# power.net
KiCad netlist of a schematic drawn in Altium Designer
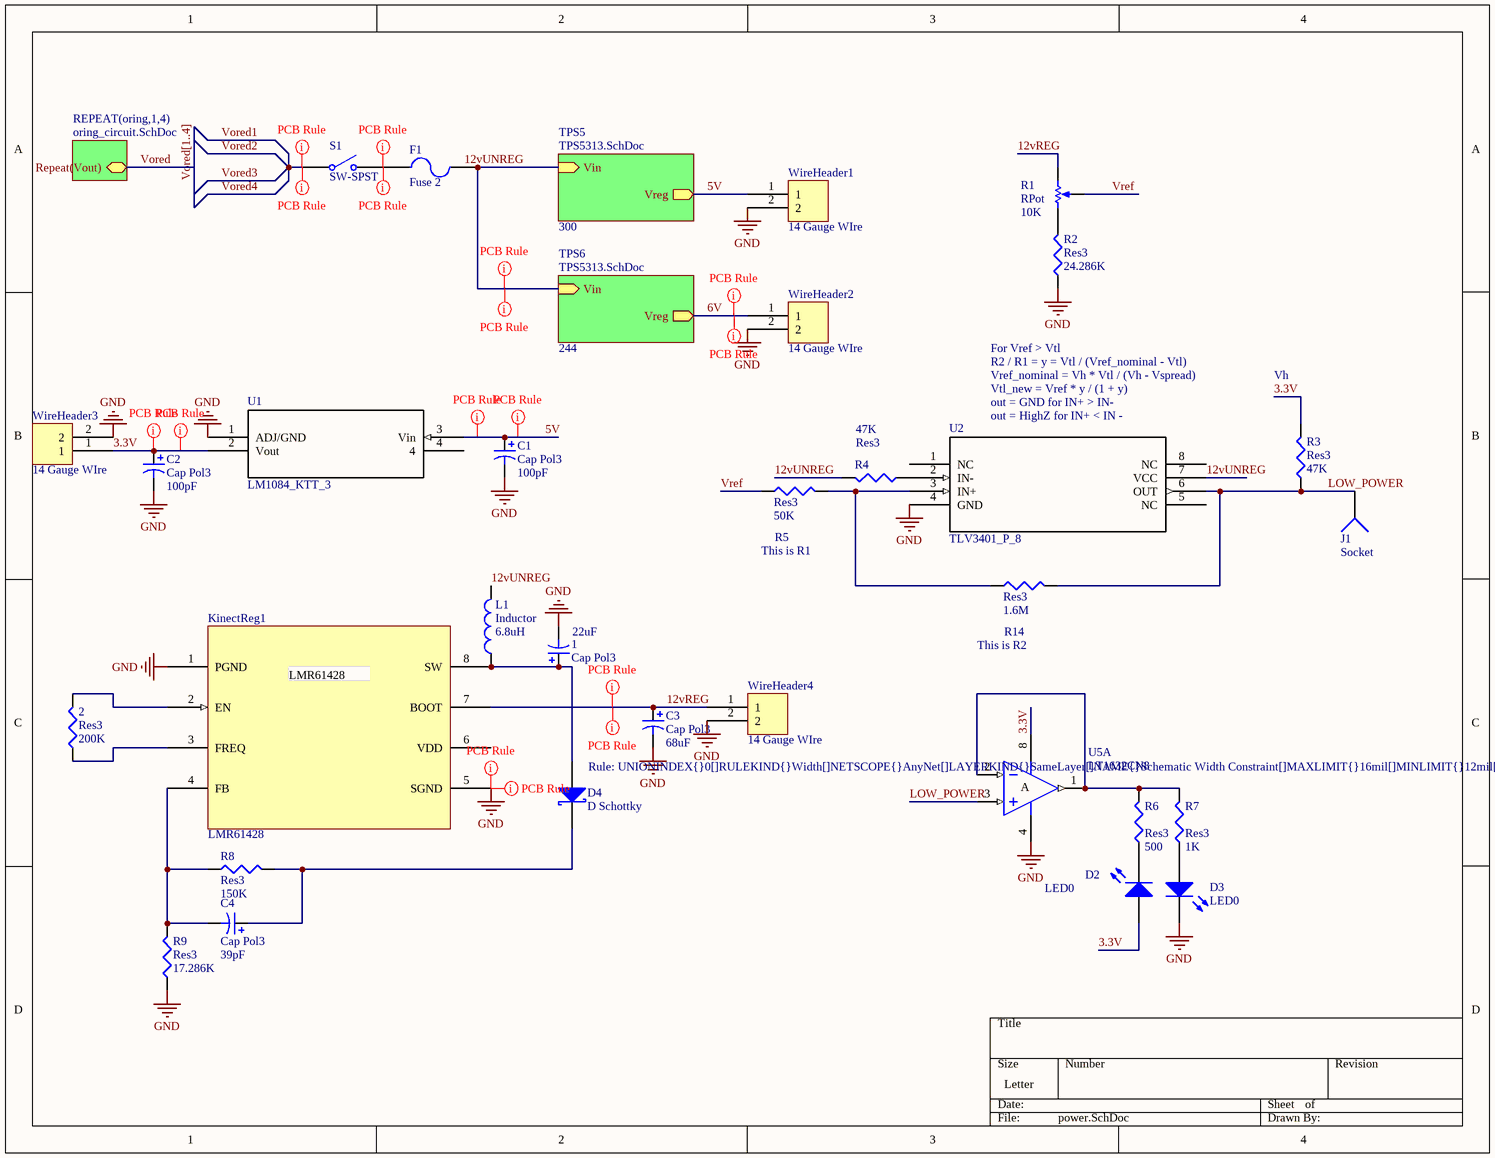
[diagram p0: power.SchDoc]

(export (version "E")
  (design (tool "Eeschema 10.0.6"))
  (components
    (comp (ref "1")
      (value "Cap Pol3")
      (footprint "C0805")
      (description "Polarized Capacitor (Surface Mount)")
      (fields (field (name "ALTIUM_VALUE") "22uF") (field (name "PUBLISHER") "Altium Limited"))
      (libsource (lib "Miscellaneous Devices") (part "Cap Pol3"))
    )
    (comp (ref "2")
      (value "Res3")
      (footprint "6-0805_M")
      (description "Resistor")
      (fields (field (name "ALTIUM_VALUE") "200K") (field (name "PUBLISHER") "Altium Limited"))
      (libsource (lib "Miscellaneous Devices") (part "Res3"))
    )
    (comp (ref "C1")
      (value "Cap Pol3")
      (footprint "C0805")
      (description "Polarized Capacitor (Surface Mount)")
      (fields (field (name "ALTIUM_VALUE") "100pF") (field (name "PUBLISHER") "Altium Limited"))
      (libsource (lib "Miscellaneous Devices") (part "Cap Pol3"))
    )
    (comp (ref "C2")
      (value "Cap Pol3")
      (footprint "C0805")
      (description "Polarized Capacitor (Surface Mount)")
      (fields (field (name "ALTIUM_VALUE") "100pF") (field (name "PUBLISHER") "Altium Limited"))
      (libsource (lib "Miscellaneous Devices") (part "Cap Pol3"))
    )
    (comp (ref "C3")
      (value "Cap Pol3")
      (footprint "C0805")
      (description "Polarized Capacitor (Surface Mount)")
      (fields (field (name "ALTIUM_VALUE") "68uF") (field (name "PUBLISHER") "Altium Limited"))
      (libsource (lib "Miscellaneous Devices") (part "Cap Pol3"))
    )
    (comp (ref "C4")
      (value "Cap Pol3")
      (footprint "C0805")
      (description "Polarized Capacitor (Surface Mount)")
      (fields (field (name "ALTIUM_VALUE") "39pF") (field (name "PUBLISHER") "Altium Limited"))
      (libsource (lib "Miscellaneous Devices") (part "Cap Pol3"))
    )
    (comp (ref "D2")
      (value "LED0")
      (footprint "LED-0")
      (description "Typical INFRARED GaAs LED")
      (fields (field (name "PUBLISHER") "Altium Limited"))
      (libsource (lib "Miscellaneous Devices") (part "LED0"))
    )
    (comp (ref "D3")
      (value "LED0")
      (footprint "LED-0")
      (description "Typical INFRARED GaAs LED")
      (fields (field (name "PUBLISHER") "Altium Limited"))
      (libsource (lib "Miscellaneous Devices") (part "LED0"))
    )
    (comp (ref "D4")
      (value "D Schottky")
      (footprint "AXIAL-0.3")
      (description "Schottky Diode")
      (fields (field (name "PUBLISHER") "Altium Limited"))
      (libsource (lib "Miscellaneous Devices") (part "D Schottky"))
    )
    (comp (ref "F1")
      (value "Fuse 2")
      (footprint "PIN-W2/E2.8")
      (description "Fuse")
      (fields (field (name "PUBLISHER") "Altium Limited"))
      (libsource (lib "Miscellaneous Devices") (part "Fuse 2"))
    )
    (comp (ref "J1")
      (value "Socket")
      (footprint "PIN1")
      (fields (field (name "PUBLISHER") "Altium Limited"))
      (libsource (lib "Miscellaneous Connectors") (part "Socket"))
    )
    (comp (ref "KinectReg1")
      (value "LMR61428")
      (footprint "D8")
      (libsource (lib "InvestiGator") (part "LMR61428"))
    )
    (comp (ref "L1")
      (value "Inductor")
      (footprint "6-0805_L")
      (fields (field (name "ALTIUM_VALUE") "6.8uH") (field (name "PUBLISHER") "Altium Limited"))
      (libsource (lib "Miscellaneous Devices") (part "Inductor"))
    )
    (comp (ref "R1")
      (value "RPot")
      (footprint "RPot")
      (description "Potentiometer")
      (fields (field (name "ALTIUM_VALUE") "10K") (field (name "PUBLISHER") "Altium Limited"))
      (libsource (lib "Miscellaneous Devices") (part "RPot"))
    )
    (comp (ref "R2")
      (value "Res3")
      (footprint "6-0805_M")
      (description "Resistor")
      (fields (field (name "ALTIUM_VALUE") "24.286K") (field (name "PUBLISHER") "Altium Limited"))
      (libsource (lib "Miscellaneous Devices") (part "Res3"))
    )
    (comp (ref "R3")
      (value "Res3")
      (footprint "6-0805_M")
      (description "Resistor")
      (fields (field (name "ALTIUM_VALUE") "47K") (field (name "PUBLISHER") "Altium Limited"))
      (libsource (lib "Miscellaneous Devices") (part "Res3"))
    )
    (comp (ref "R4")
      (value "Res3")
      (footprint "6-0805_M")
      (description "Resistor")
      (fields (field (name "ALTIUM_VALUE") "47K") (field (name "PUBLISHER") "Altium Limited"))
      (libsource (lib "Miscellaneous Devices") (part "Res3"))
    )
    (comp (ref "R5")
      (value "Res3")
      (footprint "6-0805_M")
      (description "Resistor")
      (fields (field (name "ALTIUM_VALUE") "50K") (field (name "PUBLISHER") "Altium Limited"))
      (libsource (lib "Miscellaneous Devices") (part "Res3"))
    )
    (comp (ref "R6")
      (value "Res3")
      (footprint "6-0805_M")
      (description "Resistor")
      (fields (field (name "ALTIUM_VALUE") "500") (field (name "PUBLISHER") "Altium Limited"))
      (libsource (lib "Miscellaneous Devices") (part "Res3"))
    )
    (comp (ref "R7")
      (value "Res3")
      (footprint "6-0805_M")
      (description "Resistor")
      (fields (field (name "ALTIUM_VALUE") "1K") (field (name "PUBLISHER") "Altium Limited"))
      (libsource (lib "Miscellaneous Devices") (part "Res3"))
    )
    (comp (ref "R8")
      (value "Res3")
      (footprint "6-0805_M")
      (description "Resistor")
      (fields (field (name "ALTIUM_VALUE") "150K") (field (name "PUBLISHER") "Altium Limited"))
      (libsource (lib "Miscellaneous Devices") (part "Res3"))
    )
    (comp (ref "R9")
      (value "Res3")
      (footprint "6-0805_M")
      (description "Resistor")
      (fields (field (name "ALTIUM_VALUE") "17.286K") (field (name "PUBLISHER") "Altium Limited"))
      (libsource (lib "Miscellaneous Devices") (part "Res3"))
    )
    (comp (ref "R14")
      (value "Res3")
      (footprint "6-0805_M")
      (description "Resistor")
      (fields (field (name "ALTIUM_VALUE") "1.6M") (field (name "PUBLISHER") "Altium Limited"))
      (libsource (lib "Miscellaneous Devices") (part "Res3"))
    )
    (comp (ref "S1")
      (value "SW-SPST")
      (footprint "switch")
      (description "Single-Pole, Single-Throw Switch")
      (fields (field (name "PUBLISHER") "Altium Limited"))
      (libsource (lib "Miscellaneous Devices") (part "SW-SPST"))
    )
    (comp (ref "U1")
      (value "LM1084_KTT_3")
      (footprint "TS3B")
      (description "Imported")
      (fields (field (name "PARTNUMBER") "LM1084IS-33"))
      (libsource (lib "LM1084") (part "LM1084_KTT_3"))
    )
    (comp (ref "U2")
      (value "TLV3401_P_8")
      (footprint "P8")
      (description "Imported")
      (fields
        (field (name "MANUFACTURER_PART_NUMBER") "tlv3401_p_8")
        (field (name "GENERIC_PART_NUMBER") "TLV3401")
      )
      (libsource (lib "TLV3401P") (part "TLV3401_P_8"))
    )
    (comp (ref "U5")
      (value "LT1632CN8")
      (footprint "P8")
      (description "45MHz, 45V/µs, Dual Rail-to-Rail Input and Output Precision Operational Amplifier")
      (fields (field (name "PUBLISHER") "Altium Limited"))
      (libsource (lib "ECE Lib (1)") (part "LT1632CN8"))
    )
    (comp (ref "WireHeader1")
      (value "14 Gauge WIre")
      (footprint "WireHeader")
      (libsource (lib "InvestiGator") (part "WireHeader"))
    )
    (comp (ref "WireHeader2")
      (value "14 Gauge WIre")
      (footprint "WireHeader")
      (libsource (lib "InvestiGator") (part "WireHeader"))
    )
    (comp (ref "WireHeader3")
      (value "14 Gauge WIre")
      (footprint "WireHeader")
      (libsource (lib "") (part "WireHeader_1"))
    )
    (comp (ref "WireHeader4")
      (value "14 Gauge WIre")
      (footprint "WireHeader")
      (libsource (lib "InvestiGator") (part "WireHeader"))
    )
  )
  (nets
    (net (code "1") (name "/3.3V") (class "Default")
      (node (ref "C2") (pin "1") (pinfunction "1_1") (pintype "passive"))
      (node (ref "D2") (pin "1") (pinfunction "A_1") (pintype "passive"))
      (node (ref "R3") (pin "2") (pinfunction "2_2") (pintype "passive"))
      (node (ref "U1") (pin "2") (pinfunction "Vout_2") (pintype "passive"))
      (node (ref "U5") (pin "8") (pinfunction "V+_8") (pintype "power_in"))
      (node (ref "WireHeader3") (pin "1") (pinfunction "1_1") (pintype "passive"))
    )
    (net (code "2") (name "/5V") (class "Default")
      (node (ref "C1") (pin "1") (pinfunction "1_1") (pintype "passive"))
      (node (ref "U1") (pin "3") (pinfunction "Vin_3") (pintype "input"))
      (node (ref "WireHeader1") (pin "1") (pinfunction "1_1") (pintype "passive"))
    )
    (net (code "3") (name "/6V") (class "Default")
      (node (ref "WireHeader2") (pin "1") (pinfunction "1_1") (pintype "passive"))
    )
    (net (code "4") (name "/12vREG") (class "Default")
      (node (ref "C3") (pin "1") (pinfunction "1_1") (pintype "passive"))
      (node (ref "KinectReg1") (pin "7") (pinfunction "BOOT_7") (pintype "passive"))
      (node (ref "R1") (pin "2") (pinfunction "BOT_2") (pintype "passive"))
      (node (ref "WireHeader4") (pin "1") (pinfunction "1_1") (pintype "passive"))
    )
    (net (code "5") (name "/12vUNREG") (class "Default")
      (node (ref "L1") (pin "2") (pinfunction "2_2") (pintype "passive"))
      (node (ref "R4") (pin "2") (pinfunction "2_2") (pintype "passive"))
      (node (ref "U2") (pin "7") (pinfunction "VCC_7") (pintype "power_in"))
    )
    (net (code "6") (name "/LOW_POWER") (class "Default")
      (node (ref "J1") (pin "1") (pinfunction "1_1") (pintype "passive"))
      (node (ref "R14") (pin "2") (pinfunction "2_2") (pintype "passive"))
      (node (ref "R3") (pin "1") (pinfunction "1_1") (pintype "passive"))
      (node (ref "U2") (pin "6") (pinfunction "OUT_6") (pintype "output"))
      (node (ref "U5") (pin "3") (pinfunction "IN+_3") (pintype "input"))
    )
    (net (code "7") (name "/Vin") (class "Default")
      (node (ref "F1") (pin "2") (pinfunction "2_2") (pintype "passive"))
    )
    (net (code "9") (name "/Vored4") (class "Default")
      (node (ref "S1") (pin "1") (pinfunction "COMMON_1") (pintype "passive"))
    )
    (net (code "11") (name "/Vref") (class "Default")
      (node (ref "R1") (pin "3") (pinfunction "TAP_3") (pintype "passive"))
      (node (ref "R5") (pin "1") (pinfunction "1_1") (pintype "passive"))
    )
    (net (code "12") (name "GND") (class "Default")
      (node (ref "1") (pin "2") (pinfunction "2_2") (pintype "passive"))
      (node (ref "C1") (pin "2") (pinfunction "2_2") (pintype "passive"))
      (node (ref "C2") (pin "2") (pinfunction "2_2") (pintype "passive"))
      (node (ref "C3") (pin "2") (pinfunction "2_2") (pintype "passive"))
      (node (ref "D3") (pin "2") (pinfunction "K_2") (pintype "passive"))
      (node (ref "KinectReg1") (pin "1") (pinfunction "PGND_1") (pintype "power_in"))
      (node (ref "KinectReg1") (pin "5") (pinfunction "SGND_5") (pintype "power_in"))
      (node (ref "R2") (pin "1") (pinfunction "1_1") (pintype "passive"))
      (node (ref "R9") (pin "1") (pinfunction "1_1") (pintype "passive"))
      (node (ref "U1") (pin "1") (pinfunction "ADJ/GND_1") (pintype "passive"))
      (node (ref "U2") (pin "4") (pinfunction "GND_4") (pintype "power_in"))
      (node (ref "U5") (pin "4") (pinfunction "V-_4") (pintype "power_in"))
      (node (ref "WireHeader1") (pin "2") (pinfunction "2_2") (pintype "passive"))
      (node (ref "WireHeader2") (pin "2") (pinfunction "2_2") (pintype "passive"))
      (node (ref "WireHeader3") (pin "2") (pinfunction "2_2") (pintype "passive"))
      (node (ref "WireHeader4") (pin "2") (pinfunction "2_2") (pintype "passive"))
    )
    (net (code "13") (name "Net-(D2-K)") (class "Default")
      (node (ref "D2") (pin "2") (pinfunction "K_2") (pintype "passive"))
      (node (ref "R6") (pin "1") (pinfunction "1_1") (pintype "passive"))
    )
    (net (code "14") (name "Net-(D3-A)") (class "Default")
      (node (ref "D3") (pin "1") (pinfunction "A_1") (pintype "passive"))
      (node (ref "R7") (pin "1") (pinfunction "1_1") (pintype "passive"))
    )
    (net (code "15") (name "Net-(D4-A)") (class "Default")
      (node (ref "1") (pin "1") (pinfunction "1_1") (pintype "passive"))
      (node (ref "D4") (pin "1") (pinfunction "A_1") (pintype "passive"))
      (node (ref "KinectReg1") (pin "8") (pinfunction "SW_8") (pintype "passive"))
      (node (ref "L1") (pin "1") (pinfunction "1_1") (pintype "passive"))
    )
    (net (code "16") (name "Net-(D4-K)") (class "Default")
      (node (ref "C4") (pin "1") (pinfunction "1_1") (pintype "passive"))
      (node (ref "D4") (pin "2") (pinfunction "K_2") (pintype "passive"))
      (node (ref "R8") (pin "2") (pinfunction "2_2") (pintype "passive"))
    )
    (net (code "17") (name "Net-(KinectReg1-EN)") (class "Default")
      (node (ref "2") (pin "2") (pinfunction "2_2") (pintype "passive"))
      (node (ref "KinectReg1") (pin "2") (pinfunction "EN_2") (pintype "input"))
    )
    (net (code "18") (name "Net-(KinectReg1-FB)") (class "Default")
      (node (ref "C4") (pin "2") (pinfunction "2_2") (pintype "passive"))
      (node (ref "KinectReg1") (pin "4") (pinfunction "FB_4") (pintype "passive"))
      (node (ref "R8") (pin "1") (pinfunction "1_1") (pintype "passive"))
      (node (ref "R9") (pin "2") (pinfunction "2_2") (pintype "passive"))
    )
    (net (code "19") (name "Net-(KinectReg1-FREQ)") (class "Default")
      (node (ref "2") (pin "1") (pinfunction "1_1") (pintype "passive"))
      (node (ref "KinectReg1") (pin "3") (pinfunction "FREQ_3") (pintype "passive"))
    )
    (net (code "20") (name "Net-(R1-TOP)") (class "Default")
      (node (ref "R1") (pin "1") (pinfunction "TOP_1") (pintype "passive"))
      (node (ref "R2") (pin "2") (pinfunction "2_2") (pintype "passive"))
    )
    (net (code "21") (name "Net-(S1-NO)") (class "Default")
      (node (ref "F1") (pin "1") (pinfunction "1_1") (pintype "passive"))
      (node (ref "S1") (pin "2") (pinfunction "NO_2") (pintype "passive"))
    )
    (net (code "22") (name "Net-(U2-IN+)") (class "Default")
      (node (ref "R14") (pin "1") (pinfunction "1_1") (pintype "passive"))
      (node (ref "R5") (pin "2") (pinfunction "2_2") (pintype "passive"))
      (node (ref "U2") (pin "3") (pinfunction "IN+_3") (pintype "input"))
    )
    (net (code "23") (name "Net-(U2-IN-)") (class "Default")
      (node (ref "R4") (pin "1") (pinfunction "1_1") (pintype "passive"))
      (node (ref "U2") (pin "2") (pinfunction "IN-_2") (pintype "input"))
    )
    (net (code "24") (name "Net-(U5A-IN-)") (class "Default")
      (node (ref "R6") (pin "2") (pinfunction "2_2") (pintype "passive"))
      (node (ref "R7") (pin "2") (pinfunction "2_2") (pintype "passive"))
      (node (ref "U5") (pin "1") (pinfunction "OUT_1") (pintype "output"))
      (node (ref "U5") (pin "2") (pinfunction "IN-_2") (pintype "input"))
    )
    (net (code "25") (name "unconnected-(KinectReg1-VDD-Pad6)") (class "Default")
      (node (ref "KinectReg1") (pin "6") (pinfunction "VDD_6") (pintype "power_in"))
    )
    (net (code "26") (name "unconnected-(U1-Pad4)") (class "Default")
      (node (ref "U1") (pin "4") (pinfunction "4_4") (pintype "passive"))
    )
    (net (code "27") (name "unconnected-(U2-NC-Pad1)") (class "Default")
      (node (ref "U2") (pin "1") (pinfunction "NC_1") (pintype "passive"))
    )
    (net (code "28") (name "unconnected-(U2-NC-Pad5)") (class "Default")
      (node (ref "U2") (pin "5") (pinfunction "NC_5") (pintype "passive"))
    )
    (net (code "29") (name "unconnected-(U2-NC-Pad8)") (class "Default")
      (node (ref "U2") (pin "8") (pinfunction "NC_8") (pintype "passive"))
    )
  )
)
